# solenoid.net
KiCad netlist of a schematic drawn in EAGLE
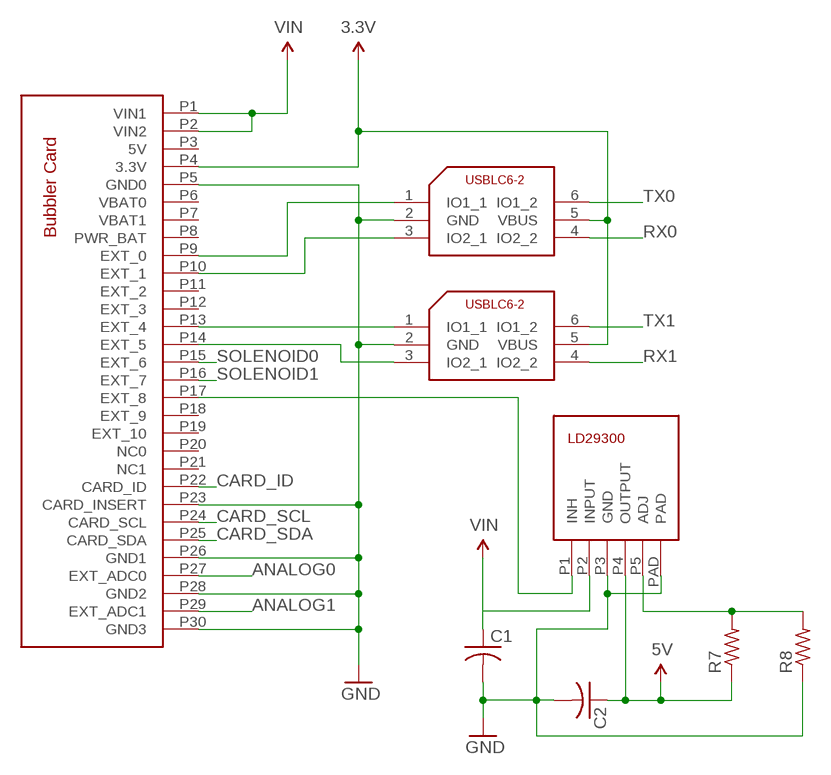
[diagram p0: schematic, sheet 1]
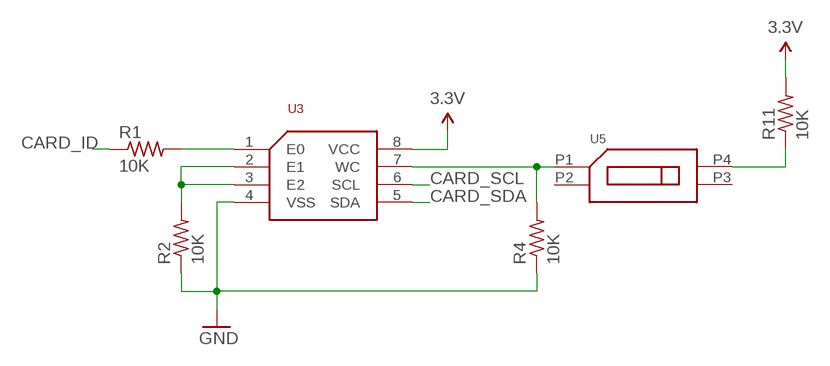
[diagram p1: schematic, sheet 2]
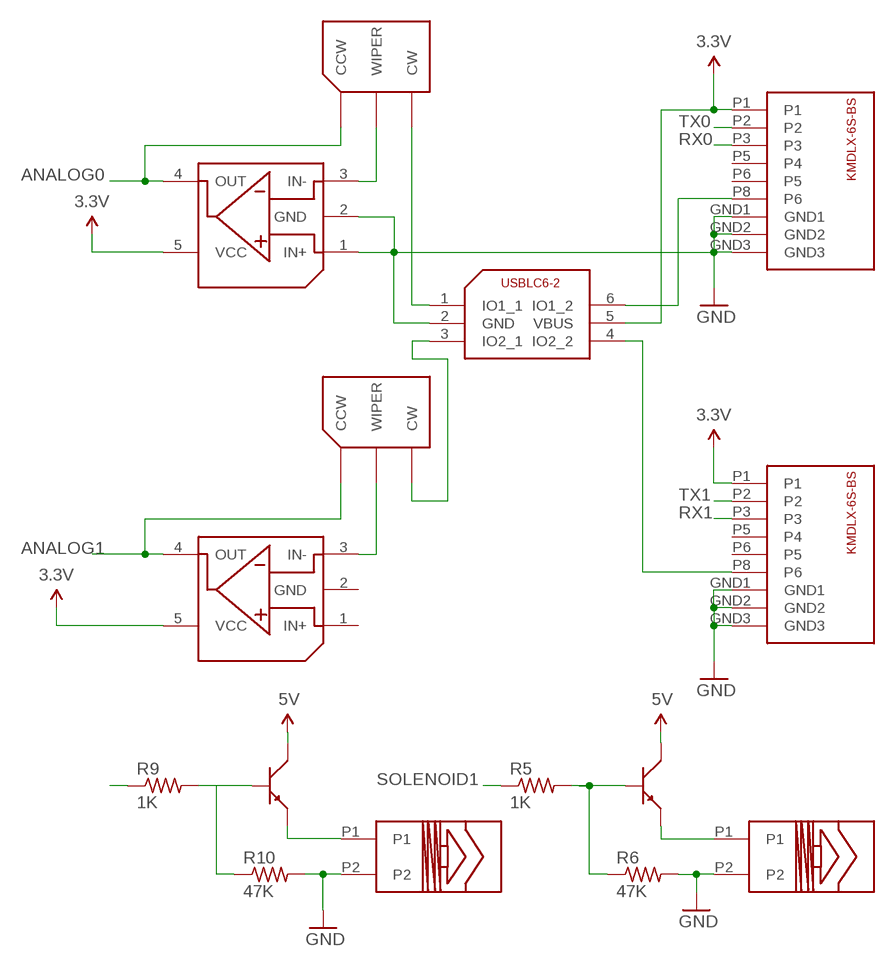
[diagram p2: schematic, sheet 3]

(export (version "E")
  (design (tool "Eeschema 10.0.6"))
  (components
    (comp (ref "R5")
      (value "1K")
      (footprint "eagle-import:R0402")
      (libsource (lib "eagle-import") (part "R-US_R0402"))
    )
    (comp (ref "R6")
      (value "47K")
      (footprint "eagle-import:R0402")
      (libsource (lib "eagle-import") (part "R-US_R0402"))
    )
    (comp (ref "R9")
      (value "1K")
      (footprint "eagle-import:R0402")
      (libsource (lib "eagle-import") (part "R-US_R0402"))
    )
    (comp (ref "R10")
      (value "47K")
      (footprint "eagle-import:R0402")
      (libsource (lib "eagle-import") (part "R-US_R0402"))
    )
    (comp (ref "U$1")
      (value "KMDLX-6S-BS")
      (footprint "eagle-import:KMDLX-6S-BS")
      (libsource (lib "eagle-import") (part "KMDLX-6S-BS"))
    )
    (comp (ref "U$4")
      (value "KMDLX-6S-BS")
      (footprint "eagle-import:KMDLX-6S-BS")
      (libsource (lib "eagle-import") (part "KMDLX-6S-BS"))
    )
    (comp (ref "U$5")
      (value "PARKER-XVALVE-8MM")
      (footprint "eagle-import:PARKER-XVALVE-8MM")
      (libsource (lib "eagle-import") (part "PARKER-XVALVE-8MM"))
    )
    (comp (ref "U$7")
      (value "PARKER-XVALVE-8MM")
      (footprint "eagle-import:PARKER-XVALVE-8MM")
      (libsource (lib "eagle-import") (part "PARKER-XVALVE-8MM"))
    )
    (comp (ref "U2")
      (value "OPAMP-ST-LMV321ILT")
      (footprint "eagle-import:SOT23-5L")
      (libsource (lib "eagle-import") (part "OPAMP-ST-LMV321ILT"))
    )
    (comp (ref "U4")
      (value "OPAMP-ST-LMV321ILT")
      (footprint "eagle-import:SOT23-5L")
      (libsource (lib "eagle-import") (part "OPAMP-ST-LMV321ILT"))
    )
    (comp (ref "U6")
      (value "BIPOLAR-PMBT6428")
      (footprint "eagle-import:DUBLIB_SOT23")
      (libsource (lib "eagle-import") (part "BIPOLAR-PMBT6428"))
    )
    (comp (ref "U8")
      (value "BIPOLAR-PMBT6428")
      (footprint "eagle-import:DUBLIB_SOT23")
      (libsource (lib "eagle-import") (part "BIPOLAR-PMBT6428"))
    )
    (comp (ref "U9")
      (value "USBLC6-2")
      (footprint "eagle-import:SOT23-6L")
      (libsource (lib "eagle-import") (part "USBLC6-2"))
    )
    (comp (ref "U12")
      (value "BOURNES-TC73")
      (footprint "eagle-import:TC73X")
      (libsource (lib "eagle-import") (part "BOURNES-TC73"))
    )
    (comp (ref "U13")
      (value "BOURNES-TC73")
      (footprint "eagle-import:TC73X")
      (libsource (lib "eagle-import") (part "BOURNES-TC73"))
    )
    (comp (ref "R1")
      (value "10K")
      (footprint "eagle-import:R0402")
      (libsource (lib "eagle-import") (part "R-US_R0402"))
    )
    (comp (ref "R2")
      (value "10K")
      (footprint "eagle-import:R0402")
      (libsource (lib "eagle-import") (part "R-US_R0402"))
    )
    (comp (ref "R4")
      (value "10K")
      (footprint "eagle-import:R0402")
      (libsource (lib "eagle-import") (part "R-US_R0402"))
    )
    (comp (ref "R11")
      (value "10K")
      (footprint "eagle-import:R0402")
      (libsource (lib "eagle-import") (part "R-US_R0402"))
    )
    (comp (ref "U3")
      (value "EEPROM-ST-M24C64")
      (footprint "eagle-import:TSSOP8")
      (libsource (lib "eagle-import") (part "EEPROM-ST-M24C64"))
    )
    (comp (ref "U5")
      (value "SWITCH-DIP-GDH-02")
      (footprint "eagle-import:SWITCH-DIP-GDH-02")
      (libsource (lib "eagle-import") (part "SWITCH-DIP-GDH-02"))
    )
    (comp (ref "C1")
      (value "C-USC0805")
      (footprint "eagle-import:C0805")
      (libsource (lib "eagle-import") (part "C-USC0805"))
    )
    (comp (ref "C2")
      (value "C-USC0805")
      (footprint "eagle-import:C0805")
      (libsource (lib "eagle-import") (part "C-USC0805"))
    )
    (comp (ref "R7")
      (value "R-US_R0402")
      (footprint "eagle-import:R0402")
      (libsource (lib "eagle-import") (part "R-US_R0402"))
    )
    (comp (ref "R8")
      (value "R-US_R0402")
      (footprint "eagle-import:R0402")
      (libsource (lib "eagle-import") (part "R-US_R0402"))
    )
    (comp (ref "U$3")
      (value "LD29300P2MTR")
      (footprint "eagle-import:P2PAK_A")
      (libsource (lib "eagle-import") (part "LD29300P2MTR"))
    )
    (comp (ref "U1")
      (value "BUBBLER_CARD")
      (footprint "eagle-import:CONNECTOR-JAE-TX24-30M")
      (libsource (lib "eagle-import") (part "BUBBLER_CARD"))
    )
    (comp (ref "U10")
      (value "USBLC6-2")
      (footprint "eagle-import:SOT23-6L")
      (libsource (lib "eagle-import") (part "USBLC6-2"))
    )
    (comp (ref "U11")
      (value "USBLC6-2")
      (footprint "eagle-import:SOT23-6L")
      (libsource (lib "eagle-import") (part "USBLC6-2"))
    )
  )
  (nets
    (net (code "1") (name "3.3V") (class "Default")
      (node (ref "R11") (pin "2") (pinfunction "2_2") (pintype "passive"))
      (node (ref "U$1") (pin "P1") (pinfunction "P1_P1") (pintype "bidirectional"))
      (node (ref "U$4") (pin "P1") (pinfunction "P1_P1") (pintype "bidirectional"))
      (node (ref "U1") (pin "P4") (pinfunction "3.3V_P4") (pintype "bidirectional"))
      (node (ref "U10") (pin "5") (pinfunction "VBUS_5") (pintype "bidirectional"))
      (node (ref "U11") (pin "5") (pinfunction "VBUS_5") (pintype "bidirectional"))
      (node (ref "U2") (pin "5") (pinfunction "VCC_5") (pintype "bidirectional"))
      (node (ref "U3") (pin "8") (pinfunction "VCC_8") (pintype "bidirectional"))
      (node (ref "U4") (pin "5") (pinfunction "VCC_5") (pintype "bidirectional"))
      (node (ref "U9") (pin "5") (pinfunction "VBUS_5") (pintype "bidirectional"))
    )
    (net (code "2") (name "5V") (class "Default")
      (node (ref "C2") (pin "1") (pinfunction "1_1") (pintype "passive"))
      (node (ref "R7") (pin "1") (pinfunction "1_1") (pintype "passive"))
      (node (ref "U$3") (pin "P4") (pinfunction "OUTPUT_P4") (pintype "bidirectional"))
      (node (ref "U6") (pin "3") (pinfunction "3_3") (pintype "bidirectional"))
      (node (ref "U8") (pin "3") (pinfunction "3_3") (pintype "bidirectional"))
    )
    (net (code "3") (name "ANALOG0") (class "Default")
      (node (ref "U1") (pin "P27") (pinfunction "EXT_ADC0_P27") (pintype "bidirectional"))
      (node (ref "U13") (pin "P$1") (pinfunction "CCW_P$1") (pintype "bidirectional"))
      (node (ref "U4") (pin "4") (pinfunction "OUT_4") (pintype "bidirectional"))
    )
    (net (code "4") (name "ANALOG1") (class "Default")
      (node (ref "U1") (pin "P29") (pinfunction "EXT_ADC1_P29") (pintype "bidirectional"))
      (node (ref "U12") (pin "P$1") (pinfunction "CCW_P$1") (pintype "bidirectional"))
      (node (ref "U2") (pin "4") (pinfunction "OUT_4") (pintype "bidirectional"))
    )
    (net (code "5") (name "CARD_ID") (class "Default")
      (node (ref "R1") (pin "1") (pinfunction "1_1") (pintype "passive"))
      (node (ref "U1") (pin "P22") (pinfunction "CARD_ID_P22") (pintype "bidirectional"))
    )
    (net (code "6") (name "CARD_SCL") (class "Default")
      (node (ref "U1") (pin "P24") (pinfunction "CARD_SCL_P24") (pintype "bidirectional"))
      (node (ref "U3") (pin "6") (pinfunction "SCL_6") (pintype "bidirectional"))
    )
    (net (code "7") (name "CARD_SDA") (class "Default")
      (node (ref "U1") (pin "P25") (pinfunction "CARD_SDA_P25") (pintype "bidirectional"))
      (node (ref "U3") (pin "5") (pinfunction "SDA_5") (pintype "bidirectional"))
    )
    (net (code "8") (name "GND") (class "Default")
      (node (ref "C1") (pin "2") (pinfunction "2_2") (pintype "passive"))
      (node (ref "C2") (pin "2") (pinfunction "2_2") (pintype "passive"))
      (node (ref "R10") (pin "2") (pinfunction "2_2") (pintype "passive"))
      (node (ref "R2") (pin "1") (pinfunction "1_1") (pintype "passive"))
      (node (ref "R4") (pin "1") (pinfunction "1_1") (pintype "passive"))
      (node (ref "R6") (pin "2") (pinfunction "2_2") (pintype "passive"))
      (node (ref "R8") (pin "1") (pinfunction "1_1") (pintype "passive"))
      (node (ref "U$1") (pin "GND1") (pinfunction "GND1_GND1") (pintype "bidirectional"))
      (node (ref "U$1") (pin "GND2") (pinfunction "GND2_GND2") (pintype "bidirectional"))
      (node (ref "U$1") (pin "GND3") (pinfunction "GND3_GND3") (pintype "bidirectional"))
      (node (ref "U$3") (pin "P3") (pinfunction "GND_P3") (pintype "bidirectional"))
      (node (ref "U$3") (pin "PAD") (pinfunction "PAD_PAD") (pintype "bidirectional"))
      (node (ref "U$4") (pin "GND1") (pinfunction "GND1_GND1") (pintype "bidirectional"))
      (node (ref "U$4") (pin "GND2") (pinfunction "GND2_GND2") (pintype "bidirectional"))
      (node (ref "U$4") (pin "GND3") (pinfunction "GND3_GND3") (pintype "bidirectional"))
      (node (ref "U$5") (pin "P2") (pinfunction "P2_P2") (pintype "bidirectional"))
      (node (ref "U$7") (pin "P2") (pinfunction "P2_P2") (pintype "bidirectional"))
      (node (ref "U1") (pin "P23") (pinfunction "CARD_INSERT_P23") (pintype "bidirectional"))
      (node (ref "U1") (pin "P26") (pinfunction "GND1_P26") (pintype "bidirectional"))
      (node (ref "U1") (pin "P28") (pinfunction "GND2_P28") (pintype "bidirectional"))
      (node (ref "U1") (pin "P30") (pinfunction "GND3_P30") (pintype "bidirectional"))
      (node (ref "U1") (pin "P5") (pinfunction "GND0_P5") (pintype "bidirectional"))
      (node (ref "U10") (pin "2") (pinfunction "GND_2") (pintype "bidirectional"))
      (node (ref "U11") (pin "2") (pinfunction "GND_2") (pintype "bidirectional"))
      (node (ref "U3") (pin "4") (pinfunction "VSS_4") (pintype "bidirectional"))
      (node (ref "U4") (pin "1") (pinfunction "IN+_1") (pintype "bidirectional"))
      (node (ref "U4") (pin "2") (pinfunction "GND_2") (pintype "bidirectional"))
      (node (ref "U9") (pin "2") (pinfunction "GND_2") (pintype "bidirectional"))
    )
    (net (code "9") (name "Net-(R5-Pad2)") (class "Default")
      (node (ref "R5") (pin "2") (pinfunction "2_2") (pintype "passive"))
      (node (ref "R6") (pin "1") (pinfunction "1_1") (pintype "passive"))
      (node (ref "U6") (pin "1") (pinfunction "1_1") (pintype "bidirectional"))
    )
    (net (code "10") (name "Net-(R10-Pad1)") (class "Default")
      (node (ref "R10") (pin "1") (pinfunction "1_1") (pintype "passive"))
      (node (ref "R9") (pin "2") (pinfunction "2_2") (pintype "passive"))
      (node (ref "U8") (pin "1") (pinfunction "1_1") (pintype "bidirectional"))
    )
    (net (code "11") (name "Net-(U$1-P6)") (class "Default")
      (node (ref "U$1") (pin "P8") (pinfunction "P6_P8") (pintype "bidirectional"))
      (node (ref "U9") (pin "6") (pinfunction "IO1_2_6") (pintype "bidirectional"))
    )
    (net (code "12") (name "Net-(U$3-ADJ)") (class "Default")
      (node (ref "R7") (pin "2") (pinfunction "2_2") (pintype "passive"))
      (node (ref "R8") (pin "2") (pinfunction "2_2") (pintype "passive"))
      (node (ref "U$3") (pin "P5") (pinfunction "ADJ_P5") (pintype "bidirectional"))
    )
    (net (code "13") (name "Net-(U$3-INH)") (class "Default")
      (node (ref "U$3") (pin "P1") (pinfunction "INH_P1") (pintype "bidirectional"))
      (node (ref "U1") (pin "P17") (pinfunction "EXT_8_P17") (pintype "bidirectional"))
    )
    (net (code "14") (name "Net-(U$4-P6)") (class "Default")
      (node (ref "U$4") (pin "P8") (pinfunction "P6_P8") (pintype "bidirectional"))
      (node (ref "U9") (pin "4") (pinfunction "IO2_2_4") (pintype "bidirectional"))
    )
    (net (code "15") (name "Net-(U$5-PadP1)") (class "Default")
      (node (ref "U$5") (pin "P1") (pinfunction "P1_P1") (pintype "bidirectional"))
      (node (ref "U6") (pin "2") (pinfunction "2_2") (pintype "bidirectional"))
    )
    (net (code "16") (name "Net-(U$7-PadP1)") (class "Default")
      (node (ref "U$7") (pin "P1") (pinfunction "P1_P1") (pintype "bidirectional"))
      (node (ref "U8") (pin "2") (pinfunction "2_2") (pintype "bidirectional"))
    )
    (net (code "17") (name "Net-(U1-EXT_0)") (class "Default")
      (node (ref "U1") (pin "P9") (pinfunction "EXT_0_P9") (pintype "bidirectional"))
      (node (ref "U10") (pin "1") (pinfunction "IO1_1_1") (pintype "bidirectional"))
    )
    (net (code "18") (name "Net-(U1-EXT_1)") (class "Default")
      (node (ref "U1") (pin "P10") (pinfunction "EXT_1_P10") (pintype "bidirectional"))
      (node (ref "U10") (pin "3") (pinfunction "IO2_1_3") (pintype "bidirectional"))
    )
    (net (code "19") (name "Net-(U1-EXT_4)") (class "Default")
      (node (ref "U1") (pin "P13") (pinfunction "EXT_4_P13") (pintype "bidirectional"))
      (node (ref "U11") (pin "1") (pinfunction "IO1_1_1") (pintype "bidirectional"))
    )
    (net (code "20") (name "Net-(U1-EXT_5)") (class "Default")
      (node (ref "U1") (pin "P14") (pinfunction "EXT_5_P14") (pintype "bidirectional"))
      (node (ref "U11") (pin "3") (pinfunction "IO2_1_3") (pintype "bidirectional"))
    )
    (net (code "21") (name "Net-(U3-E0)") (class "Default")
      (node (ref "R1") (pin "2") (pinfunction "2_2") (pintype "passive"))
      (node (ref "U3") (pin "1") (pinfunction "E0_1") (pintype "bidirectional"))
    )
    (net (code "22") (name "Net-(U3-E1)") (class "Default")
      (node (ref "R2") (pin "2") (pinfunction "2_2") (pintype "passive"))
      (node (ref "U3") (pin "2") (pinfunction "E1_2") (pintype "bidirectional"))
      (node (ref "U3") (pin "3") (pinfunction "E2_3") (pintype "bidirectional"))
    )
    (net (code "23") (name "Net-(U3-WC)") (class "Default")
      (node (ref "R4") (pin "2") (pinfunction "2_2") (pintype "passive"))
      (node (ref "U3") (pin "7") (pinfunction "WC_7") (pintype "bidirectional"))
      (node (ref "U5") (pin "P1") (pinfunction "SW0_0_P1") (pintype "bidirectional"))
    )
    (net (code "24") (name "Net-(U5-SW0_1)") (class "Default")
      (node (ref "R11") (pin "1") (pinfunction "1_1") (pintype "passive"))
      (node (ref "U5") (pin "P4") (pinfunction "SW0_1_P4") (pintype "bidirectional"))
    )
    (net (code "25") (name "Net-(U12-CW)") (class "Default")
      (node (ref "U12") (pin "P$3") (pinfunction "CW_P$3") (pintype "bidirectional"))
      (node (ref "U9") (pin "3") (pinfunction "IO2_1_3") (pintype "bidirectional"))
    )
    (net (code "26") (name "Net-(U12-WIPER)") (class "Default")
      (node (ref "U12") (pin "P$2") (pinfunction "WIPER_P$2") (pintype "bidirectional"))
      (node (ref "U2") (pin "3") (pinfunction "IN-_3") (pintype "bidirectional"))
    )
    (net (code "27") (name "Net-(U13-CW)") (class "Default")
      (node (ref "U13") (pin "P$3") (pinfunction "CW_P$3") (pintype "bidirectional"))
      (node (ref "U9") (pin "1") (pinfunction "IO1_1_1") (pintype "bidirectional"))
    )
    (net (code "28") (name "Net-(U13-WIPER)") (class "Default")
      (node (ref "U13") (pin "P$2") (pinfunction "WIPER_P$2") (pintype "bidirectional"))
      (node (ref "U4") (pin "3") (pinfunction "IN-_3") (pintype "bidirectional"))
    )
    (net (code "29") (name "RX0") (class "Default")
      (node (ref "U$1") (pin "P3") (pinfunction "P3_P3") (pintype "bidirectional"))
      (node (ref "U10") (pin "4") (pinfunction "IO2_2_4") (pintype "bidirectional"))
    )
    (net (code "30") (name "RX1") (class "Default")
      (node (ref "U$4") (pin "P3") (pinfunction "P3_P3") (pintype "bidirectional"))
      (node (ref "U11") (pin "4") (pinfunction "IO2_2_4") (pintype "bidirectional"))
    )
    (net (code "31") (name "SOLENOID0") (class "Default")
      (node (ref "R9") (pin "1") (pinfunction "1_1") (pintype "passive"))
      (node (ref "U1") (pin "P15") (pinfunction "EXT_6_P15") (pintype "bidirectional"))
    )
    (net (code "32") (name "SOLENOID1") (class "Default")
      (node (ref "R5") (pin "1") (pinfunction "1_1") (pintype "passive"))
      (node (ref "U1") (pin "P16") (pinfunction "EXT_7_P16") (pintype "bidirectional"))
    )
    (net (code "33") (name "TX0") (class "Default")
      (node (ref "U$1") (pin "P2") (pinfunction "P2_P2") (pintype "bidirectional"))
      (node (ref "U10") (pin "6") (pinfunction "IO1_2_6") (pintype "bidirectional"))
    )
    (net (code "34") (name "TX1") (class "Default")
      (node (ref "U$4") (pin "P2") (pinfunction "P2_P2") (pintype "bidirectional"))
      (node (ref "U11") (pin "6") (pinfunction "IO1_2_6") (pintype "bidirectional"))
    )
    (net (code "35") (name "VIN") (class "Default")
      (node (ref "C1") (pin "1") (pinfunction "1_1") (pintype "passive"))
      (node (ref "U$3") (pin "P2") (pinfunction "INPUT_P2") (pintype "bidirectional"))
      (node (ref "U1") (pin "P1") (pinfunction "VIN1_P1") (pintype "bidirectional"))
      (node (ref "U1") (pin "P2") (pinfunction "VIN2_P2") (pintype "bidirectional"))
    )
    (net (code "36") (name "unconnected-(U$1-P4-PadP5)") (class "Default")
      (node (ref "U$1") (pin "P5") (pinfunction "P4_P5") (pintype "bidirectional"))
    )
    (net (code "37") (name "unconnected-(U$1-P5-PadP6)") (class "Default")
      (node (ref "U$1") (pin "P6") (pinfunction "P5_P6") (pintype "bidirectional"))
    )
    (net (code "38") (name "unconnected-(U$4-P4-PadP5)") (class "Default")
      (node (ref "U$4") (pin "P5") (pinfunction "P4_P5") (pintype "bidirectional"))
    )
    (net (code "39") (name "unconnected-(U$4-P5-PadP6)") (class "Default")
      (node (ref "U$4") (pin "P6") (pinfunction "P5_P6") (pintype "bidirectional"))
    )
    (net (code "40") (name "unconnected-(U1-5V-PadP3)") (class "Default")
      (node (ref "U1") (pin "P3") (pinfunction "5V_P3") (pintype "bidirectional"))
    )
    (net (code "41") (name "unconnected-(U1-EXT_2-PadP11)") (class "Default")
      (node (ref "U1") (pin "P11") (pinfunction "EXT_2_P11") (pintype "bidirectional"))
    )
    (net (code "42") (name "unconnected-(U1-EXT_3-PadP12)") (class "Default")
      (node (ref "U1") (pin "P12") (pinfunction "EXT_3_P12") (pintype "bidirectional"))
    )
    (net (code "43") (name "unconnected-(U1-EXT_9-PadP18)") (class "Default")
      (node (ref "U1") (pin "P18") (pinfunction "EXT_9_P18") (pintype "bidirectional"))
    )
    (net (code "44") (name "unconnected-(U1-EXT_10-PadP19)") (class "Default")
      (node (ref "U1") (pin "P19") (pinfunction "EXT_10_P19") (pintype "bidirectional"))
    )
    (net (code "45") (name "unconnected-(U1-NC0-PadP20)") (class "Default")
      (node (ref "U1") (pin "P20") (pinfunction "NC0_P20") (pintype "bidirectional"))
    )
    (net (code "46") (name "unconnected-(U1-NC1-PadP21)") (class "Default")
      (node (ref "U1") (pin "P21") (pinfunction "NC1_P21") (pintype "bidirectional"))
    )
    (net (code "47") (name "unconnected-(U1-PWR_BAT-PadP8)") (class "Default")
      (node (ref "U1") (pin "P8") (pinfunction "PWR_BAT_P8") (pintype "bidirectional"))
    )
    (net (code "48") (name "unconnected-(U1-VBAT0-PadP6)") (class "Default")
      (node (ref "U1") (pin "P6") (pinfunction "VBAT0_P6") (pintype "bidirectional"))
    )
    (net (code "49") (name "unconnected-(U1-VBAT1-PadP7)") (class "Default")
      (node (ref "U1") (pin "P7") (pinfunction "VBAT1_P7") (pintype "bidirectional"))
    )
    (net (code "50") (name "unconnected-(U2-GND-Pad2)") (class "Default")
      (node (ref "U2") (pin "2") (pinfunction "GND_2") (pintype "bidirectional"))
    )
    (net (code "51") (name "unconnected-(U2-IN+-Pad1)") (class "Default")
      (node (ref "U2") (pin "1") (pinfunction "IN+_1") (pintype "bidirectional"))
    )
    (net (code "52") (name "unconnected-(U5-SW1_0-PadP2)") (class "Default")
      (node (ref "U5") (pin "P2") (pinfunction "SW1_0_P2") (pintype "bidirectional"))
    )
    (net (code "53") (name "unconnected-(U5-SW1_1-PadP3)") (class "Default")
      (node (ref "U5") (pin "P3") (pinfunction "SW1_1_P3") (pintype "bidirectional"))
    )
  )
)
